# 04_GPIOs.net
KiCad netlist of a schematic drawn in Altium Designer
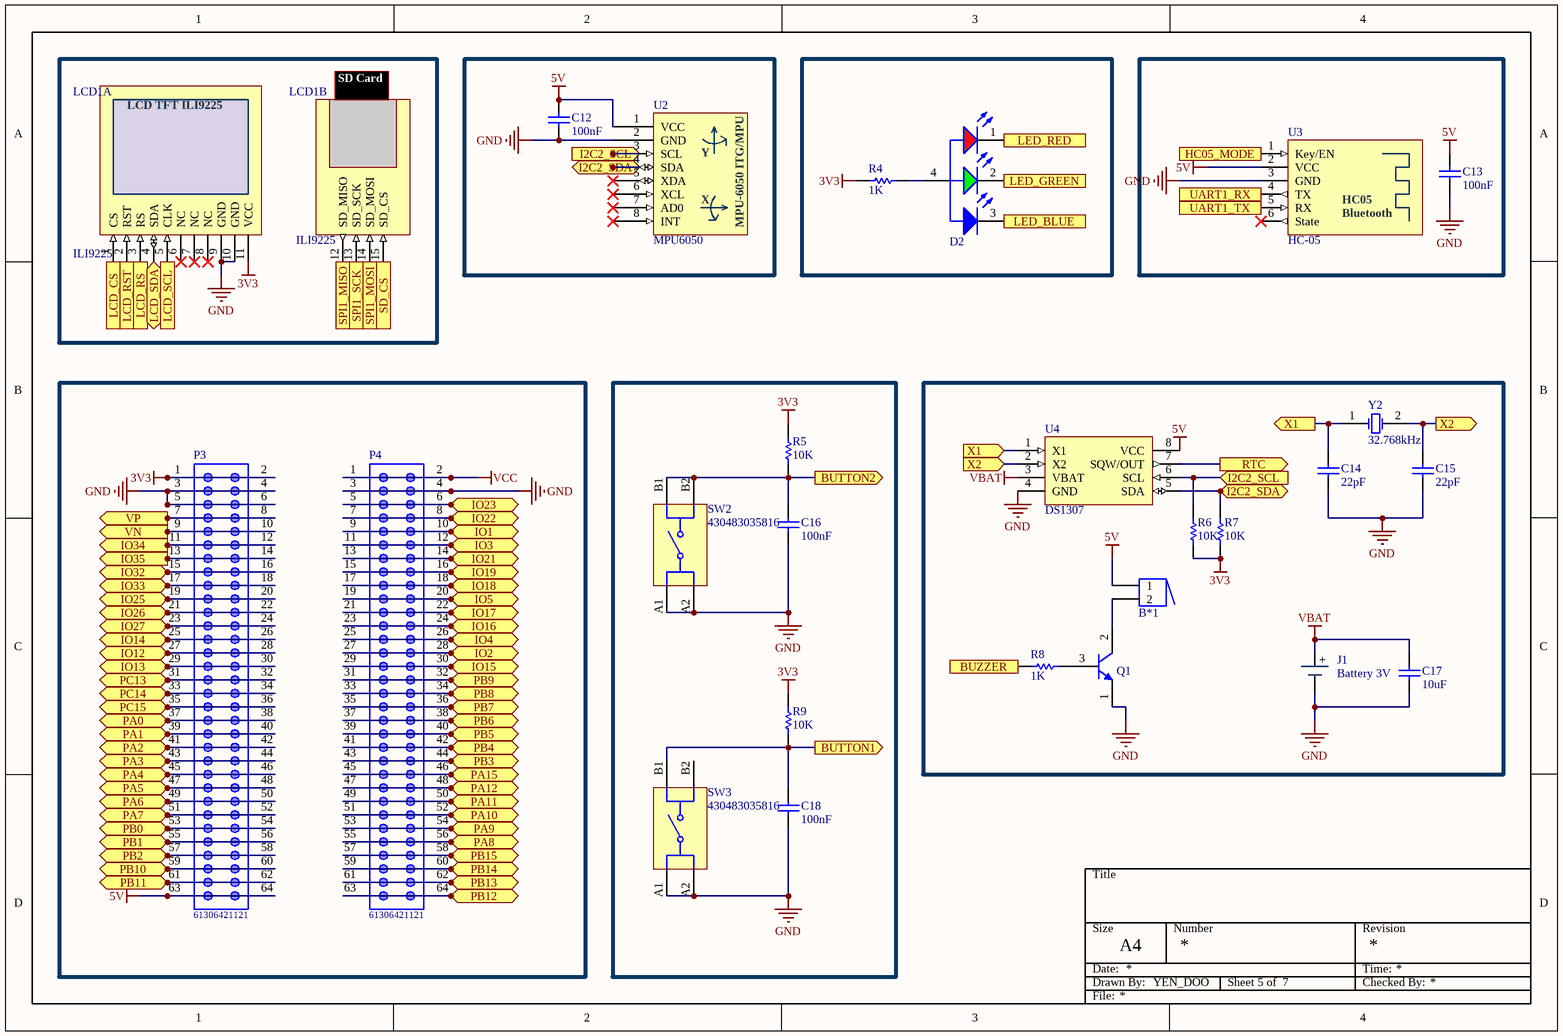
[diagram p0: 04_GPIOs.SchDoc]

(export (version "E")
  (design (tool "Eeschema 10.0.6"))
  (components
    (comp (ref "B*1") (value "Buzzer") (footprint "BUZZER") (libsource (lib "PIF_Library") (part "Buzzer")))
    (comp (ref "C12")
      (value "100nF")
      (footprint "CAP-SM-0805")
      (description "Capacitor")
      (fields (field (name "Comment") "Cap Non-Pol SMD"))
      (libsource (lib "PIF_Library") (part "Cap Non-Pol SMD"))
    )
    (comp (ref "C13")
      (value "100nF")
      (footprint "CAP-SM-0805")
      (description "Capacitor")
      (fields (field (name "Comment") "Cap Non-Pol SMD"))
      (libsource (lib "PIF_Library") (part "Cap Non-Pol SMD"))
    )
    (comp (ref "C14")
      (value "22pF")
      (footprint "CAP-SM-0805")
      (description "Capacitor")
      (fields (field (name "Comment") "Cap Non-Pol SMD"))
      (libsource (lib "PIF_Library") (part "Cap Non-Pol SMD"))
    )
    (comp (ref "C15")
      (value "22pF")
      (footprint "CAP-SM-0805")
      (description "Capacitor")
      (fields (field (name "Comment") "Cap Non-Pol SMD"))
      (libsource (lib "PIF_Library") (part "Cap Non-Pol SMD"))
    )
    (comp (ref "C16")
      (value "100nF")
      (footprint "CAP-SM-0805")
      (description "Capacitor")
      (fields (field (name "Comment") "Cap Non-Pol SMD"))
      (libsource (lib "PIF_Library") (part "Cap Non-Pol SMD"))
    )
    (comp (ref "C17")
      (value "10uF")
      (footprint "CAP-SM-0805")
      (description "Capacitor")
      (fields (field (name "Comment") "Cap Non-Pol SMD"))
      (libsource (lib "PIF_Library") (part "Cap Non-Pol SMD"))
    )
    (comp (ref "C18")
      (value "100nF")
      (footprint "CAP-SM-0805")
      (description "Capacitor")
      (fields (field (name "Comment") "Cap Non-Pol SMD"))
      (libsource (lib "PIF_Library") (part "Cap Non-Pol SMD"))
    )
    (comp (ref "D2")
      (value "Red & Green & Blue, 120°")
      (footprint "WL-SFCD_0805")
      (description "WL-SFCD SMT Full-color Chip LED Diffused, size 0805, Red & Green & Blue, 120°")
      (fields
        (field (name "MANUFACTURER PART NUMBER") "150080M153000")
        (field (name "MANUFACTURER") "Wurth Elektronik")
      )
      (libsource (lib "Altium_WL-SFCD (rev22c)") (part "150080M153000"))
    )
    (comp (ref "J1")
      (value "Battery 3V")
      (footprint "SocketPin3V")
      (description "Socket CR1220 SMD")
      (libsource (lib "YenDoo") (part "Battery-3V"))
    )
    (comp (ref "LCD1")
      (value "ILI9225")
      (footprint "LCD TFT ILI9225")
      (libsource (lib "YenDoo") (part "LCD TFT"))
    )
    (comp (ref "P3")
      (value "61306421121")
      (footprint "61306421121")
      (description "WR-PHD Pin Header, THT, pitch 2.54mm, Dual Row, Vertical, 64p")
      (fields (field (name "MANUFACTURER") "Wurth Elektronik"))
      (libsource (lib "Altium_WR-PHD (rev20a)") (part "61306421121"))
    )
    (comp (ref "P4")
      (value "61306421121")
      (footprint "61306421121")
      (description "WR-PHD Pin Header, THT, pitch 2.54mm, Dual Row, Vertical, 64p")
      (fields (field (name "MANUFACTURER") "Wurth Elektronik"))
      (libsource (lib "Altium_WR-PHD (rev20a)") (part "61306421121"))
    )
    (comp (ref "Q1")
      (value "C1815")
      (footprint "SOT23B")
      (description "NPN Bipolar Transistor")
      (libsource (lib "PIF_Library") (part "C1815"))
    )
    (comp (ref "R4")
      (value "1K")
      (footprint "RES-SM-0805")
      (description "Resistor")
      (fields (field (name "Comment") "RESISTOR SMD"))
      (libsource (lib "PIF_Library") (part "RESISTOR SMD"))
    )
    (comp (ref "R5")
      (value "10K")
      (footprint "RES-SM-0805")
      (description "Resistor")
      (fields (field (name "Comment") "RESISTOR SMD"))
      (libsource (lib "PIF_Library") (part "RESISTOR SMD"))
    )
    (comp (ref "R6")
      (value "10K")
      (footprint "RES-SM-0805")
      (description "Resistor")
      (fields (field (name "Comment") "RESISTOR SMD"))
      (libsource (lib "PIF_Library") (part "RESISTOR SMD"))
    )
    (comp (ref "R7")
      (value "10K")
      (footprint "RES-SM-0805")
      (description "Resistor")
      (fields (field (name "Comment") "RESISTOR SMD"))
      (libsource (lib "PIF_Library") (part "RESISTOR SMD"))
    )
    (comp (ref "R8")
      (value "1K")
      (footprint "RES-SM-0805")
      (description "Resistor")
      (fields (field (name "Comment") "RESISTOR SMD"))
      (libsource (lib "PIF_Library") (part "RESISTOR SMD"))
    )
    (comp (ref "R9")
      (value "10K")
      (footprint "RES-SM-0805")
      (description "Resistor")
      (fields (field (name "Comment") "RESISTOR SMD"))
      (libsource (lib "PIF_Library") (part "RESISTOR SMD"))
    )
    (comp (ref "SW2")
      (value "430483035816")
      (footprint "WS-TASV_L6W6H3.5_4304x30358x6")
      (description "WS-TASV J-Bend SMT Washable Tact Switch, 12VDC, 50mA, 160g, height 3.5mm")
      (fields (field (name "MANUFACTURER") "Wurth Elektronik"))
      (libsource (lib "Altium_WS-TASV (rev22a)") (part "430483035816"))
    )
    (comp (ref "SW3")
      (value "430483035816")
      (footprint "WS-TASV_L6W6H3.5_4304x30358x6")
      (description "WS-TASV J-Bend SMT Washable Tact Switch, 12VDC, 50mA, 160g, height 3.5mm")
      (fields (field (name "MANUFACTURER") "Wurth Elektronik"))
      (libsource (lib "Altium_WS-TASV (rev22a)") (part "430483035816"))
    )
    (comp (ref "U2")
      (value "MPU6050")
      (footprint "MPU-6050")
      (fields (field (name "MFR") "DFRobot") (field (name "UTILIZED IC / PART") "MPU-6050"))
      (libsource (lib "YenDoo") (part "MPU6050"))
    )
    (comp (ref "U3") (value "HC-05") (footprint "HC-05") (libsource (lib "YenDoo") (part "HC-05")))
    (comp (ref "U4")
      (value "DS1307")
      (footprint "SOIC-4")
      (description "Real Time Clock (RTC) IC Clock/Calendar 56B I²C, 2-Wire Serial 8-SDIP (0.300\", 7.62mm)")
      (fields (field (name "MFR") "Analog Devices Inc./Maxim Integrated"))
      (libsource (lib "YenDoo") (part "DS1307"))
    )
    (comp (ref "Y2")
      (value "32.768kHz")
      (footprint "WE-XTAL_WATCH_830002997B")
      (description "WE-XTAL Watch Crystal, THT, WATCH, 32.768kHz, +/-20ppm")
      (fields
        (field (name "MANUFACTURER PART NUMBER") "830002997B")
        (field (name "MANUFACTURER") "Wurth Elektronik")
      )
      (libsource (lib "Altium_WE-XTAL (rev20c)") (part "830002997B"))
    )
  )
  (nets
    (net (code "1") (name "/BUTTON1") (class "Default")
      (node (ref "C18") (pin "2") (pinfunction "2_2") (pintype "passive"))
      (node (ref "R9") (pin "1") (pinfunction "1_1") (pintype "passive"))
      (node (ref "SW3") (pin "B1") (pinfunction "B1_B1") (pintype "passive"))
    )
    (net (code "2") (name "/BUTTON2") (class "Default")
      (node (ref "C16") (pin "2") (pinfunction "2_2") (pintype "passive"))
      (node (ref "R5") (pin "1") (pinfunction "1_1") (pintype "passive"))
      (node (ref "SW2") (pin "B1") (pinfunction "B1_B1") (pintype "passive"))
      (node (ref "SW2") (pin "B2") (pinfunction "B2_B2") (pintype "passive"))
    )
    (net (code "3") (name "/BUZZER") (class "Default")
      (node (ref "R8") (pin "2") (pinfunction "2_2") (pintype "passive"))
    )
    (net (code "4") (name "/HC05_MODE") (class "Default")
      (node (ref "U3") (pin "1") (pinfunction "Key/EN_1") (pintype "input"))
    )
    (net (code "5") (name "/I2C2_SCL") (class "Default")
      (node (ref "R6") (pin "1") (pinfunction "1_1") (pintype "passive"))
      (node (ref "U2") (pin "3") (pinfunction "SCL_3") (pintype "input"))
      (node (ref "U4") (pin "6") (pinfunction "SCL_6") (pintype "input"))
    )
    (net (code "6") (name "/I2C2_SDA") (class "Default")
      (node (ref "R7") (pin "1") (pinfunction "1_1") (pintype "passive"))
      (node (ref "U2") (pin "4") (pinfunction "SDA_4") (pintype "bidirectional"))
      (node (ref "U4") (pin "5") (pinfunction "SDA_5") (pintype "bidirectional"))
    )
    (net (code "7") (name "/IO1") (class "Default")
      (node (ref "P4") (pin "10") (pinfunction "10_10") (pintype "passive"))
      (node (ref "P4") (pin "9") (pinfunction "9_9") (pintype "passive"))
    )
    (net (code "8") (name "/IO2") (class "Default")
      (node (ref "P4") (pin "27") (pinfunction "27_27") (pintype "passive"))
      (node (ref "P4") (pin "28") (pinfunction "28_28") (pintype "passive"))
    )
    (net (code "9") (name "/IO3") (class "Default")
      (node (ref "P4") (pin "11") (pinfunction "11_11") (pintype "passive"))
      (node (ref "P4") (pin "12") (pinfunction "12_12") (pintype "passive"))
    )
    (net (code "10") (name "/IO4") (class "Default")
      (node (ref "P4") (pin "25") (pinfunction "25_25") (pintype "passive"))
      (node (ref "P4") (pin "26") (pinfunction "26_26") (pintype "passive"))
    )
    (net (code "11") (name "/IO5") (class "Default")
      (node (ref "P4") (pin "19") (pinfunction "19_19") (pintype "passive"))
      (node (ref "P4") (pin "20") (pinfunction "20_20") (pintype "passive"))
    )
    (net (code "12") (name "/IO12") (class "Default")
      (node (ref "P3") (pin "27") (pinfunction "27_27") (pintype "passive"))
      (node (ref "P3") (pin "28") (pinfunction "28_28") (pintype "passive"))
    )
    (net (code "13") (name "/IO13") (class "Default")
      (node (ref "P3") (pin "29") (pinfunction "29_29") (pintype "passive"))
      (node (ref "P3") (pin "30") (pinfunction "30_30") (pintype "passive"))
    )
    (net (code "14") (name "/IO14") (class "Default")
      (node (ref "P3") (pin "25") (pinfunction "25_25") (pintype "passive"))
      (node (ref "P3") (pin "26") (pinfunction "26_26") (pintype "passive"))
    )
    (net (code "15") (name "/IO15") (class "Default")
      (node (ref "P4") (pin "29") (pinfunction "29_29") (pintype "passive"))
      (node (ref "P4") (pin "30") (pinfunction "30_30") (pintype "passive"))
    )
    (net (code "16") (name "/IO16") (class "Default")
      (node (ref "P4") (pin "23") (pinfunction "23_23") (pintype "passive"))
      (node (ref "P4") (pin "24") (pinfunction "24_24") (pintype "passive"))
    )
    (net (code "17") (name "/IO17") (class "Default")
      (node (ref "P4") (pin "21") (pinfunction "21_21") (pintype "passive"))
      (node (ref "P4") (pin "22") (pinfunction "22_22") (pintype "passive"))
    )
    (net (code "18") (name "/IO18") (class "Default")
      (node (ref "P4") (pin "17") (pinfunction "17_17") (pintype "passive"))
      (node (ref "P4") (pin "18") (pinfunction "18_18") (pintype "passive"))
    )
    (net (code "19") (name "/IO19") (class "Default")
      (node (ref "P4") (pin "15") (pinfunction "15_15") (pintype "passive"))
      (node (ref "P4") (pin "16") (pinfunction "16_16") (pintype "passive"))
    )
    (net (code "20") (name "/IO21") (class "Default")
      (node (ref "P4") (pin "13") (pinfunction "13_13") (pintype "passive"))
      (node (ref "P4") (pin "14") (pinfunction "14_14") (pintype "passive"))
    )
    (net (code "21") (name "/IO22") (class "Default")
      (node (ref "P4") (pin "7") (pinfunction "7_7") (pintype "passive"))
      (node (ref "P4") (pin "8") (pinfunction "8_8") (pintype "passive"))
    )
    (net (code "22") (name "/IO23") (class "Default")
      (node (ref "P4") (pin "5") (pinfunction "5_5") (pintype "passive"))
      (node (ref "P4") (pin "6") (pinfunction "6_6") (pintype "passive"))
    )
    (net (code "23") (name "/IO25") (class "Default")
      (node (ref "P3") (pin "19") (pinfunction "19_19") (pintype "passive"))
      (node (ref "P3") (pin "20") (pinfunction "20_20") (pintype "passive"))
    )
    (net (code "24") (name "/IO26") (class "Default")
      (node (ref "P3") (pin "21") (pinfunction "21_21") (pintype "passive"))
      (node (ref "P3") (pin "22") (pinfunction "22_22") (pintype "passive"))
    )
    (net (code "25") (name "/IO27") (class "Default")
      (node (ref "P3") (pin "23") (pinfunction "23_23") (pintype "passive"))
      (node (ref "P3") (pin "24") (pinfunction "24_24") (pintype "passive"))
    )
    (net (code "26") (name "/IO32") (class "Default")
      (node (ref "P3") (pin "15") (pinfunction "15_15") (pintype "passive"))
      (node (ref "P3") (pin "16") (pinfunction "16_16") (pintype "passive"))
    )
    (net (code "27") (name "/IO33") (class "Default")
      (node (ref "P3") (pin "17") (pinfunction "17_17") (pintype "passive"))
      (node (ref "P3") (pin "18") (pinfunction "18_18") (pintype "passive"))
    )
    (net (code "28") (name "/IO34") (class "Default")
      (node (ref "P3") (pin "11") (pinfunction "11_11") (pintype "passive"))
      (node (ref "P3") (pin "12") (pinfunction "12_12") (pintype "passive"))
    )
    (net (code "29") (name "/IO35") (class "Default")
      (node (ref "P3") (pin "13") (pinfunction "13_13") (pintype "passive"))
      (node (ref "P3") (pin "14") (pinfunction "14_14") (pintype "passive"))
    )
    (net (code "30") (name "/LCD_CS") (class "Default")
      (node (ref "LCD1") (pin "1") (pinfunction "CS_1") (pintype "input"))
    )
    (net (code "31") (name "/LCD_RS") (class "Default")
      (node (ref "LCD1") (pin "3") (pinfunction "RS_3") (pintype "input"))
    )
    (net (code "32") (name "/LCD_RST") (class "Default")
      (node (ref "LCD1") (pin "2") (pinfunction "RST_2") (pintype "input"))
    )
    (net (code "33") (name "/LCD_SCL") (class "Default")
      (node (ref "LCD1") (pin "5") (pinfunction "CLK_5") (pintype "input"))
    )
    (net (code "34") (name "/LCD_SDA") (class "Default")
      (node (ref "LCD1") (pin "4") (pinfunction "SDA_4") (pintype "bidirectional"))
    )
    (net (code "35") (name "/LED_BLUE") (class "Default")
      (node (ref "D2") (pin "3") (pinfunction "K_3") (pintype "passive"))
    )
    (net (code "36") (name "/LED_GREEN") (class "Default")
      (node (ref "D2") (pin "2") (pinfunction "K_2") (pintype "passive"))
    )
    (net (code "37") (name "/LED_RED") (class "Default")
      (node (ref "D2") (pin "1") (pinfunction "K_1") (pintype "passive"))
    )
    (net (code "38") (name "/PA0") (class "Default")
      (node (ref "P3") (pin "37") (pinfunction "37_37") (pintype "passive"))
      (node (ref "P3") (pin "38") (pinfunction "38_38") (pintype "passive"))
    )
    (net (code "39") (name "/PA1") (class "Default")
      (node (ref "P3") (pin "39") (pinfunction "39_39") (pintype "passive"))
      (node (ref "P3") (pin "40") (pinfunction "40_40") (pintype "passive"))
    )
    (net (code "40") (name "/PA2") (class "Default")
      (node (ref "P3") (pin "41") (pinfunction "41_41") (pintype "passive"))
      (node (ref "P3") (pin "42") (pinfunction "42_42") (pintype "passive"))
    )
    (net (code "41") (name "/PA3") (class "Default")
      (node (ref "P3") (pin "43") (pinfunction "43_43") (pintype "passive"))
      (node (ref "P3") (pin "44") (pinfunction "44_44") (pintype "passive"))
    )
    (net (code "42") (name "/PA4") (class "Default")
      (node (ref "P3") (pin "45") (pinfunction "45_45") (pintype "passive"))
      (node (ref "P3") (pin "46") (pinfunction "46_46") (pintype "passive"))
    )
    (net (code "43") (name "/PA5") (class "Default")
      (node (ref "P3") (pin "47") (pinfunction "47_47") (pintype "passive"))
      (node (ref "P3") (pin "48") (pinfunction "48_48") (pintype "passive"))
    )
    (net (code "44") (name "/PA6") (class "Default")
      (node (ref "P3") (pin "49") (pinfunction "49_49") (pintype "passive"))
      (node (ref "P3") (pin "50") (pinfunction "50_50") (pintype "passive"))
    )
    (net (code "45") (name "/PA7") (class "Default")
      (node (ref "P3") (pin "51") (pinfunction "51_51") (pintype "passive"))
      (node (ref "P3") (pin "52") (pinfunction "52_52") (pintype "passive"))
    )
    (net (code "46") (name "/PA8") (class "Default")
      (node (ref "P4") (pin "55") (pinfunction "55_55") (pintype "passive"))
      (node (ref "P4") (pin "56") (pinfunction "56_56") (pintype "passive"))
    )
    (net (code "47") (name "/PA9") (class "Default")
      (node (ref "P4") (pin "53") (pinfunction "53_53") (pintype "passive"))
      (node (ref "P4") (pin "54") (pinfunction "54_54") (pintype "passive"))
    )
    (net (code "48") (name "/PA10") (class "Default")
      (node (ref "P4") (pin "51") (pinfunction "51_51") (pintype "passive"))
      (node (ref "P4") (pin "52") (pinfunction "52_52") (pintype "passive"))
    )
    (net (code "49") (name "/PA11") (class "Default")
      (node (ref "P4") (pin "49") (pinfunction "49_49") (pintype "passive"))
      (node (ref "P4") (pin "50") (pinfunction "50_50") (pintype "passive"))
    )
    (net (code "50") (name "/PA12") (class "Default")
      (node (ref "P4") (pin "47") (pinfunction "47_47") (pintype "passive"))
      (node (ref "P4") (pin "48") (pinfunction "48_48") (pintype "passive"))
    )
    (net (code "51") (name "/PA15") (class "Default")
      (node (ref "P4") (pin "45") (pinfunction "45_45") (pintype "passive"))
      (node (ref "P4") (pin "46") (pinfunction "46_46") (pintype "passive"))
    )
    (net (code "52") (name "/PB0") (class "Default")
      (node (ref "P3") (pin "53") (pinfunction "53_53") (pintype "passive"))
      (node (ref "P3") (pin "54") (pinfunction "54_54") (pintype "passive"))
    )
    (net (code "53") (name "/PB1") (class "Default")
      (node (ref "P3") (pin "55") (pinfunction "55_55") (pintype "passive"))
      (node (ref "P3") (pin "56") (pinfunction "56_56") (pintype "passive"))
    )
    (net (code "54") (name "/PB2") (class "Default")
      (node (ref "P3") (pin "57") (pinfunction "57_57") (pintype "passive"))
      (node (ref "P3") (pin "58") (pinfunction "58_58") (pintype "passive"))
    )
    (net (code "55") (name "/PB3") (class "Default")
      (node (ref "P4") (pin "43") (pinfunction "43_43") (pintype "passive"))
      (node (ref "P4") (pin "44") (pinfunction "44_44") (pintype "passive"))
    )
    (net (code "56") (name "/PB4") (class "Default")
      (node (ref "P4") (pin "41") (pinfunction "41_41") (pintype "passive"))
      (node (ref "P4") (pin "42") (pinfunction "42_42") (pintype "passive"))
    )
    (net (code "57") (name "/PB5") (class "Default")
      (node (ref "P4") (pin "39") (pinfunction "39_39") (pintype "passive"))
      (node (ref "P4") (pin "40") (pinfunction "40_40") (pintype "passive"))
    )
    (net (code "58") (name "/PB6") (class "Default")
      (node (ref "P4") (pin "37") (pinfunction "37_37") (pintype "passive"))
      (node (ref "P4") (pin "38") (pinfunction "38_38") (pintype "passive"))
    )
    (net (code "59") (name "/PB7") (class "Default")
      (node (ref "P4") (pin "35") (pinfunction "35_35") (pintype "passive"))
      (node (ref "P4") (pin "36") (pinfunction "36_36") (pintype "passive"))
    )
    (net (code "60") (name "/PB8") (class "Default")
      (node (ref "P4") (pin "33") (pinfunction "33_33") (pintype "passive"))
      (node (ref "P4") (pin "34") (pinfunction "34_34") (pintype "passive"))
    )
    (net (code "61") (name "/PB9") (class "Default")
      (node (ref "P4") (pin "31") (pinfunction "31_31") (pintype "passive"))
      (node (ref "P4") (pin "32") (pinfunction "32_32") (pintype "passive"))
    )
    (net (code "62") (name "/PB10") (class "Default")
      (node (ref "P3") (pin "59") (pinfunction "59_59") (pintype "passive"))
      (node (ref "P3") (pin "60") (pinfunction "60_60") (pintype "passive"))
    )
    (net (code "63") (name "/PB11") (class "Default")
      (node (ref "P3") (pin "61") (pinfunction "61_61") (pintype "passive"))
      (node (ref "P3") (pin "62") (pinfunction "62_62") (pintype "passive"))
    )
    (net (code "64") (name "/PB12") (class "Default")
      (node (ref "P4") (pin "63") (pinfunction "63_63") (pintype "passive"))
      (node (ref "P4") (pin "64") (pinfunction "64_64") (pintype "passive"))
    )
    (net (code "65") (name "/PB13") (class "Default")
      (node (ref "P4") (pin "61") (pinfunction "61_61") (pintype "passive"))
      (node (ref "P4") (pin "62") (pinfunction "62_62") (pintype "passive"))
    )
    (net (code "66") (name "/PB14") (class "Default")
      (node (ref "P4") (pin "59") (pinfunction "59_59") (pintype "passive"))
      (node (ref "P4") (pin "60") (pinfunction "60_60") (pintype "passive"))
    )
    (net (code "67") (name "/PB15") (class "Default")
      (node (ref "P4") (pin "57") (pinfunction "57_57") (pintype "passive"))
      (node (ref "P4") (pin "58") (pinfunction "58_58") (pintype "passive"))
    )
    (net (code "68") (name "/PC13") (class "Default")
      (node (ref "P3") (pin "31") (pinfunction "31_31") (pintype "passive"))
      (node (ref "P3") (pin "32") (pinfunction "32_32") (pintype "passive"))
    )
    (net (code "69") (name "/PC14") (class "Default")
      (node (ref "P3") (pin "33") (pinfunction "33_33") (pintype "passive"))
      (node (ref "P3") (pin "34") (pinfunction "34_34") (pintype "passive"))
    )
    (net (code "70") (name "/PC15") (class "Default")
      (node (ref "P3") (pin "35") (pinfunction "35_35") (pintype "passive"))
      (node (ref "P3") (pin "36") (pinfunction "36_36") (pintype "passive"))
    )
    (net (code "71") (name "/RTC") (class "Default")
      (node (ref "U4") (pin "7") (pinfunction "SQW/OUT_7") (pintype "output"))
    )
    (net (code "72") (name "/SD_CS") (class "Default")
      (node (ref "LCD1") (pin "15") (pinfunction "SD_CS_15") (pintype "input"))
    )
    (net (code "73") (name "/SPI1_MISO") (class "Default")
      (node (ref "LCD1") (pin "12") (pinfunction "SD_MISO_12") (pintype "output"))
    )
    (net (code "74") (name "/SPI1_MOSI") (class "Default")
      (node (ref "LCD1") (pin "14") (pinfunction "SD_MOSI_14") (pintype "input"))
    )
    (net (code "75") (name "/SPI1_SCK") (class "Default")
      (node (ref "LCD1") (pin "13") (pinfunction "SD_SCK_13") (pintype "input"))
    )
    (net (code "76") (name "/UART1_RX") (class "Default")
      (node (ref "U3") (pin "4") (pinfunction "TX_4") (pintype "output"))
    )
    (net (code "77") (name "/UART1_TX") (class "Default")
      (node (ref "U3") (pin "5") (pinfunction "RX_5") (pintype "input"))
    )
    (net (code "78") (name "/VN") (class "Default")
      (node (ref "P3") (pin "10") (pinfunction "10_10") (pintype "passive"))
      (node (ref "P3") (pin "9") (pinfunction "9_9") (pintype "passive"))
    )
    (net (code "79") (name "/VP") (class "Default")
      (node (ref "P3") (pin "7") (pinfunction "7_7") (pintype "passive"))
      (node (ref "P3") (pin "8") (pinfunction "8_8") (pintype "passive"))
    )
    (net (code "80") (name "/X1") (class "Default")
      (node (ref "C14") (pin "2") (pinfunction "2_2") (pintype "passive"))
      (node (ref "U4") (pin "1") (pinfunction "X1_1") (pintype "input"))
      (node (ref "Y2") (pin "1") (pinfunction "OSC1_1") (pintype "passive"))
    )
    (net (code "81") (name "/X2") (class "Default")
      (node (ref "C15") (pin "2") (pinfunction "2_2") (pintype "passive"))
      (node (ref "U4") (pin "2") (pinfunction "X2_2") (pintype "input"))
      (node (ref "Y2") (pin "2") (pinfunction "OSC2_2") (pintype "passive"))
    )
    (net (code "82") (name "3V3") (class "Default")
      (node (ref "LCD1") (pin "11") (pinfunction "VCC_11") (pintype "power_in"))
      (node (ref "P3") (pin "1") (pinfunction "1_1") (pintype "passive"))
      (node (ref "P3") (pin "2") (pinfunction "2_2") (pintype "passive"))
      (node (ref "R4") (pin "2") (pinfunction "2_2") (pintype "passive"))
      (node (ref "R5") (pin "2") (pinfunction "2_2") (pintype "passive"))
      (node (ref "R6") (pin "2") (pinfunction "2_2") (pintype "passive"))
      (node (ref "R7") (pin "2") (pinfunction "2_2") (pintype "passive"))
      (node (ref "R9") (pin "2") (pinfunction "2_2") (pintype "passive"))
    )
    (net (code "83") (name "5V") (class "Default")
      (node (ref "B*1") (pin "1") (pinfunction "1_1") (pintype "passive"))
      (node (ref "C12") (pin "2") (pinfunction "2_2") (pintype "passive"))
      (node (ref "C13") (pin "2") (pinfunction "2_2") (pintype "passive"))
      (node (ref "P3") (pin "63") (pinfunction "63_63") (pintype "passive"))
      (node (ref "P3") (pin "64") (pinfunction "64_64") (pintype "passive"))
      (node (ref "U2") (pin "1") (pinfunction "VCC_1") (pintype "power_in"))
      (node (ref "U3") (pin "2") (pinfunction "VCC_2") (pintype "power_in"))
      (node (ref "U4") (pin "8") (pinfunction "VCC_8") (pintype "power_in"))
    )
    (net (code "84") (name "GND") (class "Default")
      (node (ref "C12") (pin "1") (pinfunction "1_1") (pintype "passive"))
      (node (ref "C13") (pin "1") (pinfunction "1_1") (pintype "passive"))
      (node (ref "C14") (pin "1") (pinfunction "1_1") (pintype "passive"))
      (node (ref "C15") (pin "1") (pinfunction "1_1") (pintype "passive"))
      (node (ref "C16") (pin "1") (pinfunction "1_1") (pintype "passive"))
      (node (ref "C17") (pin "1") (pinfunction "1_1") (pintype "passive"))
      (node (ref "C18") (pin "1") (pinfunction "1_1") (pintype "passive"))
      (node (ref "J1") (pin "2") (pinfunction "GND_2") (pintype "passive"))
      (node (ref "LCD1") (pin "10") (pinfunction "GND_10") (pintype "power_in"))
      (node (ref "LCD1") (pin "9") (pinfunction "GND_9") (pintype "power_in"))
      (node (ref "P3") (pin "3") (pinfunction "3_3") (pintype "passive"))
      (node (ref "P3") (pin "4") (pinfunction "4_4") (pintype "passive"))
      (node (ref "P3") (pin "5") (pinfunction "5_5") (pintype "passive"))
      (node (ref "P3") (pin "6") (pinfunction "6_6") (pintype "passive"))
      (node (ref "P4") (pin "3") (pinfunction "3_3") (pintype "passive"))
      (node (ref "P4") (pin "4") (pinfunction "4_4") (pintype "passive"))
      (node (ref "Q1") (pin "1") (pinfunction "E_1") (pintype "passive"))
      (node (ref "SW2") (pin "A1") (pinfunction "A1_A1") (pintype "passive"))
      (node (ref "SW2") (pin "A2") (pinfunction "A2_A2") (pintype "passive"))
      (node (ref "SW3") (pin "A1") (pinfunction "A1_A1") (pintype "passive"))
      (node (ref "SW3") (pin "A2") (pinfunction "A2_A2") (pintype "passive"))
      (node (ref "U2") (pin "2") (pinfunction "GND_2") (pintype "power_in"))
      (node (ref "U3") (pin "3") (pinfunction "GND_3") (pintype "power_in"))
      (node (ref "U4") (pin "4") (pinfunction "GND_4") (pintype "power_in"))
    )
    (net (code "85") (name "Net-(D2-A)") (class "Default")
      (node (ref "D2") (pin "4") (pinfunction "A_4") (pintype "passive"))
      (node (ref "R4") (pin "1") (pinfunction "1_1") (pintype "passive"))
    )
    (net (code "86") (name "Net-(Q1-B)") (class "Default")
      (node (ref "Q1") (pin "3") (pinfunction "B_3") (pintype "passive"))
      (node (ref "R8") (pin "1") (pinfunction "1_1") (pintype "passive"))
    )
    (net (code "87") (name "Net-(Q1-C)") (class "Default")
      (node (ref "B*1") (pin "2") (pinfunction "2_2") (pintype "passive"))
      (node (ref "Q1") (pin "2") (pinfunction "C_2") (pintype "passive"))
    )
    (net (code "88") (name "VBAT") (class "Default")
      (node (ref "C17") (pin "2") (pinfunction "2_2") (pintype "passive"))
      (node (ref "J1") (pin "1") (pinfunction "Vcc_1") (pintype "passive"))
      (node (ref "U4") (pin "3") (pinfunction "VBAT_3") (pintype "power_in"))
    )
    (net (code "89") (name "VCC") (class "Default")
      (node (ref "P4") (pin "1") (pinfunction "1_1") (pintype "passive"))
      (node (ref "P4") (pin "2") (pinfunction "2_2") (pintype "passive"))
    )
    (net (code "90") (name "unconnected-(LCD1A-NC-Pad6)") (class "Default")
      (node (ref "LCD1") (pin "6") (pinfunction "NC_6") (pintype "passive+no_connect"))
    )
    (net (code "91") (name "unconnected-(LCD1A-NC-Pad7)") (class "Default")
      (node (ref "LCD1") (pin "7") (pinfunction "NC_7") (pintype "passive+no_connect"))
    )
    (net (code "92") (name "unconnected-(LCD1A-NC-Pad8)") (class "Default")
      (node (ref "LCD1") (pin "8") (pinfunction "NC_8") (pintype "passive+no_connect"))
    )
    (net (code "93") (name "unconnected-(SW3-PadB2)") (class "Default")
      (node (ref "SW3") (pin "B2") (pinfunction "B2_B2") (pintype "passive"))
    )
    (net (code "94") (name "unconnected-(U2-AD0-Pad7)") (class "Default")
      (node (ref "U2") (pin "7") (pinfunction "AD0_7") (pintype "input+no_connect"))
    )
    (net (code "95") (name "unconnected-(U2-INT-Pad8)") (class "Default")
      (node (ref "U2") (pin "8") (pinfunction "INT_8") (pintype "input+no_connect"))
    )
    (net (code "96") (name "unconnected-(U2-XCL-Pad6)") (class "Default")
      (node (ref "U2") (pin "6") (pinfunction "XCL_6") (pintype "input+no_connect"))
    )
    (net (code "97") (name "unconnected-(U2-XDA-Pad5)") (class "Default")
      (node (ref "U2") (pin "5") (pinfunction "XDA_5") (pintype "bidirectional+no_connect"))
    )
    (net (code "98") (name "unconnected-(U3-State-Pad6)") (class "Default")
      (node (ref "U3") (pin "6") (pinfunction "State_6") (pintype "output+no_connect"))
    )
  )
)
